# readhead.net
KiCad netlist of a schematic drawn in EAGLE
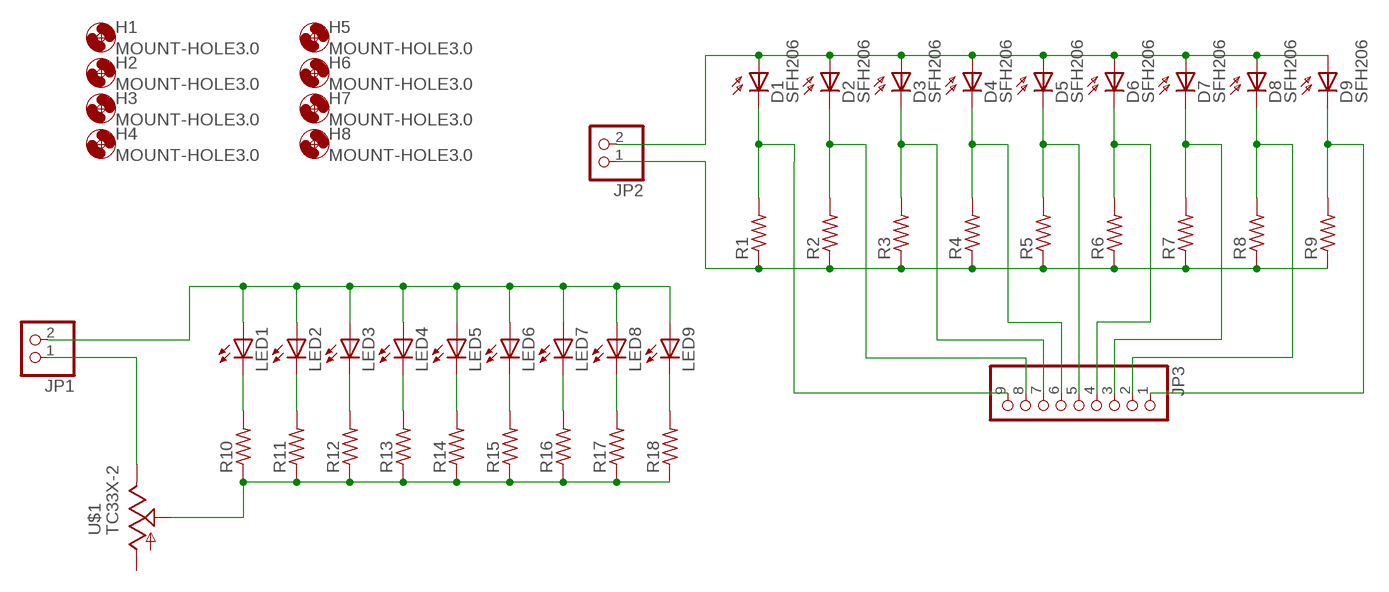
[diagram p0: schematic, sheet 1]

(export (version "E")
  (design (tool "Eeschema 10.0.6"))
  (components
    (comp (ref "D1")
      (value "SFH206")
      (footprint "eagle-import:SFH206")
      (fields (field (name "MPN") "SFH206K"))
      (libsource (lib "eagle-import") (part "SFH206"))
    )
    (comp (ref "D2")
      (value "SFH206")
      (footprint "eagle-import:SFH206")
      (fields (field (name "MPN") "SFH206K"))
      (libsource (lib "eagle-import") (part "SFH206"))
    )
    (comp (ref "D3")
      (value "SFH206")
      (footprint "eagle-import:SFH206")
      (fields (field (name "MPN") "SFH206K"))
      (libsource (lib "eagle-import") (part "SFH206"))
    )
    (comp (ref "D4")
      (value "SFH206")
      (footprint "eagle-import:SFH206")
      (fields (field (name "MPN") "SFH206K"))
      (libsource (lib "eagle-import") (part "SFH206"))
    )
    (comp (ref "D5")
      (value "SFH206")
      (footprint "eagle-import:SFH206")
      (fields (field (name "MPN") "SFH206K"))
      (libsource (lib "eagle-import") (part "SFH206"))
    )
    (comp (ref "D6")
      (value "SFH206")
      (footprint "eagle-import:SFH206")
      (fields (field (name "MPN") "SFH206K"))
      (libsource (lib "eagle-import") (part "SFH206"))
    )
    (comp (ref "D7")
      (value "SFH206")
      (footprint "eagle-import:SFH206")
      (fields (field (name "MPN") "SFH206K"))
      (libsource (lib "eagle-import") (part "SFH206"))
    )
    (comp (ref "D8")
      (value "SFH206")
      (footprint "eagle-import:SFH206")
      (fields (field (name "MPN") "SFH206K"))
      (libsource (lib "eagle-import") (part "SFH206"))
    )
    (comp (ref "D9")
      (value "SFH206")
      (footprint "eagle-import:SFH206")
      (fields (field (name "MPN") "SFH206K"))
      (libsource (lib "eagle-import") (part "SFH206"))
    )
    (comp (ref "H1")
      (value "MOUNT-HOLE3.0")
      (footprint "eagle-import:3,0")
      (libsource (lib "eagle-import") (part "MOUNT-HOLE3.0"))
    )
    (comp (ref "H2")
      (value "MOUNT-HOLE3.0")
      (footprint "eagle-import:3,0")
      (libsource (lib "eagle-import") (part "MOUNT-HOLE3.0"))
    )
    (comp (ref "H3")
      (value "MOUNT-HOLE3.0")
      (footprint "eagle-import:3,0")
      (libsource (lib "eagle-import") (part "MOUNT-HOLE3.0"))
    )
    (comp (ref "H4")
      (value "MOUNT-HOLE3.0")
      (footprint "eagle-import:3,0")
      (libsource (lib "eagle-import") (part "MOUNT-HOLE3.0"))
    )
    (comp (ref "H5")
      (value "MOUNT-HOLE3.0")
      (footprint "eagle-import:3,0")
      (libsource (lib "eagle-import") (part "MOUNT-HOLE3.0"))
    )
    (comp (ref "H6")
      (value "MOUNT-HOLE3.0")
      (footprint "eagle-import:3,0")
      (libsource (lib "eagle-import") (part "MOUNT-HOLE3.0"))
    )
    (comp (ref "H7")
      (value "MOUNT-HOLE3.0")
      (footprint "eagle-import:3,0")
      (libsource (lib "eagle-import") (part "MOUNT-HOLE3.0"))
    )
    (comp (ref "H8")
      (value "MOUNT-HOLE3.0")
      (footprint "eagle-import:3,0")
      (libsource (lib "eagle-import") (part "MOUNT-HOLE3.0"))
    )
    (comp (ref "JP1")
      (value "PINHD-1X2")
      (footprint "eagle-import:1X02")
      (libsource (lib "eagle-import") (part "PINHD-1X2"))
    )
    (comp (ref "JP2")
      (value "PINHD-1X2")
      (footprint "eagle-import:1X02")
      (libsource (lib "eagle-import") (part "PINHD-1X2"))
    )
    (comp (ref "JP3")
      (value "PINHD-1X9")
      (footprint "eagle-import:1X09")
      (libsource (lib "eagle-import") (part "PINHD-1X9"))
    )
    (comp (ref "LED1")
      (value "LED5MM")
      (footprint "eagle-import:LED5MM")
      (libsource (lib "eagle-import") (part "LED5MM"))
    )
    (comp (ref "LED2")
      (value "LED5MM")
      (footprint "eagle-import:LED5MM")
      (libsource (lib "eagle-import") (part "LED5MM"))
    )
    (comp (ref "LED3")
      (value "LED5MM")
      (footprint "eagle-import:LED5MM")
      (libsource (lib "eagle-import") (part "LED5MM"))
    )
    (comp (ref "LED4")
      (value "LED5MM")
      (footprint "eagle-import:LED5MM")
      (libsource (lib "eagle-import") (part "LED5MM"))
    )
    (comp (ref "LED5")
      (value "LED5MM")
      (footprint "eagle-import:LED5MM")
      (libsource (lib "eagle-import") (part "LED5MM"))
    )
    (comp (ref "LED6")
      (value "LED5MM")
      (footprint "eagle-import:LED5MM")
      (libsource (lib "eagle-import") (part "LED5MM"))
    )
    (comp (ref "LED7")
      (value "LED5MM")
      (footprint "eagle-import:LED5MM")
      (libsource (lib "eagle-import") (part "LED5MM"))
    )
    (comp (ref "LED8")
      (value "LED5MM")
      (footprint "eagle-import:LED5MM")
      (libsource (lib "eagle-import") (part "LED5MM"))
    )
    (comp (ref "LED9")
      (value "LED5MM")
      (footprint "eagle-import:LED5MM")
      (libsource (lib "eagle-import") (part "LED5MM"))
    )
    (comp (ref "R1")
      (value "R-US_R0805")
      (footprint "eagle-import:R0805")
      (libsource (lib "eagle-import") (part "R-US_R0805"))
    )
    (comp (ref "R2")
      (value "R-US_R0805")
      (footprint "eagle-import:R0805")
      (libsource (lib "eagle-import") (part "R-US_R0805"))
    )
    (comp (ref "R3")
      (value "R-US_R0805")
      (footprint "eagle-import:R0805")
      (libsource (lib "eagle-import") (part "R-US_R0805"))
    )
    (comp (ref "R4")
      (value "R-US_R0805")
      (footprint "eagle-import:R0805")
      (libsource (lib "eagle-import") (part "R-US_R0805"))
    )
    (comp (ref "R5")
      (value "R-US_R0805")
      (footprint "eagle-import:R0805")
      (libsource (lib "eagle-import") (part "R-US_R0805"))
    )
    (comp (ref "R6")
      (value "R-US_R0805")
      (footprint "eagle-import:R0805")
      (libsource (lib "eagle-import") (part "R-US_R0805"))
    )
    (comp (ref "R7")
      (value "R-US_R0805")
      (footprint "eagle-import:R0805")
      (libsource (lib "eagle-import") (part "R-US_R0805"))
    )
    (comp (ref "R8")
      (value "R-US_R0805")
      (footprint "eagle-import:R0805")
      (libsource (lib "eagle-import") (part "R-US_R0805"))
    )
    (comp (ref "R9")
      (value "R-US_R0805")
      (footprint "eagle-import:R0805")
      (libsource (lib "eagle-import") (part "R-US_R0805"))
    )
    (comp (ref "R10")
      (value "R-US_R0805")
      (footprint "eagle-import:R0805")
      (libsource (lib "eagle-import") (part "R-US_R0805"))
    )
    (comp (ref "R11")
      (value "R-US_R0805")
      (footprint "eagle-import:R0805")
      (libsource (lib "eagle-import") (part "R-US_R0805"))
    )
    (comp (ref "R12")
      (value "R-US_R0805")
      (footprint "eagle-import:R0805")
      (libsource (lib "eagle-import") (part "R-US_R0805"))
    )
    (comp (ref "R13")
      (value "R-US_R0805")
      (footprint "eagle-import:R0805")
      (libsource (lib "eagle-import") (part "R-US_R0805"))
    )
    (comp (ref "R14")
      (value "R-US_R0805")
      (footprint "eagle-import:R0805")
      (libsource (lib "eagle-import") (part "R-US_R0805"))
    )
    (comp (ref "R15")
      (value "R-US_R0805")
      (footprint "eagle-import:R0805")
      (libsource (lib "eagle-import") (part "R-US_R0805"))
    )
    (comp (ref "R16")
      (value "R-US_R0805")
      (footprint "eagle-import:R0805")
      (libsource (lib "eagle-import") (part "R-US_R0805"))
    )
    (comp (ref "R17")
      (value "R-US_R0805")
      (footprint "eagle-import:R0805")
      (libsource (lib "eagle-import") (part "R-US_R0805"))
    )
    (comp (ref "R18")
      (value "R-US_R0805")
      (footprint "eagle-import:R0805")
      (libsource (lib "eagle-import") (part "R-US_R0805"))
    )
    (comp (ref "U$1")
      (value "TC33X-2")
      (footprint "eagle-import:TC33X-2")
      (libsource (lib "eagle-import") (part "TC33X-2"))
    )
  )
  (nets
    (net (code "1") (name "Net-(D1-C)") (class "Default")
      (node (ref "D1") (pin "K") (pinfunction "C_K") (pintype "passive"))
      (node (ref "JP3") (pin "9") (pinfunction "9_9") (pintype "passive"))
      (node (ref "R1") (pin "2") (pinfunction "2_2") (pintype "passive"))
    )
    (net (code "2") (name "Net-(D1-PadA)") (class "Default")
      (node (ref "D1") (pin "A") (pinfunction "A_A") (pintype "passive"))
      (node (ref "D2") (pin "A") (pinfunction "A_A") (pintype "passive"))
      (node (ref "D3") (pin "A") (pinfunction "A_A") (pintype "passive"))
      (node (ref "D4") (pin "A") (pinfunction "A_A") (pintype "passive"))
      (node (ref "D5") (pin "A") (pinfunction "A_A") (pintype "passive"))
      (node (ref "D6") (pin "A") (pinfunction "A_A") (pintype "passive"))
      (node (ref "D7") (pin "A") (pinfunction "A_A") (pintype "passive"))
      (node (ref "D8") (pin "A") (pinfunction "A_A") (pintype "passive"))
      (node (ref "D9") (pin "A") (pinfunction "A_A") (pintype "passive"))
      (node (ref "JP2") (pin "2") (pinfunction "2_2") (pintype "passive"))
    )
    (net (code "3") (name "Net-(D2-C)") (class "Default")
      (node (ref "D2") (pin "K") (pinfunction "C_K") (pintype "passive"))
      (node (ref "JP3") (pin "8") (pinfunction "8_8") (pintype "passive"))
      (node (ref "R2") (pin "2") (pinfunction "2_2") (pintype "passive"))
    )
    (net (code "4") (name "Net-(D3-C)") (class "Default")
      (node (ref "D3") (pin "K") (pinfunction "C_K") (pintype "passive"))
      (node (ref "JP3") (pin "7") (pinfunction "7_7") (pintype "passive"))
      (node (ref "R3") (pin "2") (pinfunction "2_2") (pintype "passive"))
    )
    (net (code "5") (name "Net-(D4-C)") (class "Default")
      (node (ref "D4") (pin "K") (pinfunction "C_K") (pintype "passive"))
      (node (ref "JP3") (pin "6") (pinfunction "6_6") (pintype "passive"))
      (node (ref "R4") (pin "2") (pinfunction "2_2") (pintype "passive"))
    )
    (net (code "6") (name "Net-(D5-C)") (class "Default")
      (node (ref "D5") (pin "K") (pinfunction "C_K") (pintype "passive"))
      (node (ref "JP3") (pin "5") (pinfunction "5_5") (pintype "passive"))
      (node (ref "R5") (pin "2") (pinfunction "2_2") (pintype "passive"))
    )
    (net (code "7") (name "Net-(D6-C)") (class "Default")
      (node (ref "D6") (pin "K") (pinfunction "C_K") (pintype "passive"))
      (node (ref "JP3") (pin "4") (pinfunction "4_4") (pintype "passive"))
      (node (ref "R6") (pin "2") (pinfunction "2_2") (pintype "passive"))
    )
    (net (code "8") (name "Net-(D7-C)") (class "Default")
      (node (ref "D7") (pin "K") (pinfunction "C_K") (pintype "passive"))
      (node (ref "JP3") (pin "3") (pinfunction "3_3") (pintype "passive"))
      (node (ref "R7") (pin "2") (pinfunction "2_2") (pintype "passive"))
    )
    (net (code "9") (name "Net-(D8-C)") (class "Default")
      (node (ref "D8") (pin "K") (pinfunction "C_K") (pintype "passive"))
      (node (ref "JP3") (pin "2") (pinfunction "2_2") (pintype "passive"))
      (node (ref "R8") (pin "2") (pinfunction "2_2") (pintype "passive"))
    )
    (net (code "10") (name "Net-(D9-C)") (class "Default")
      (node (ref "D9") (pin "K") (pinfunction "C_K") (pintype "passive"))
      (node (ref "JP3") (pin "1") (pinfunction "1_1") (pintype "passive"))
      (node (ref "R9") (pin "2") (pinfunction "2_2") (pintype "passive"))
    )
    (net (code "11") (name "Net-(JP1-Pad2)") (class "Default")
      (node (ref "JP1") (pin "2") (pinfunction "2_2") (pintype "passive"))
      (node (ref "LED1") (pin "A") (pinfunction "A_A") (pintype "passive"))
      (node (ref "LED2") (pin "A") (pinfunction "A_A") (pintype "passive"))
      (node (ref "LED3") (pin "A") (pinfunction "A_A") (pintype "passive"))
      (node (ref "LED4") (pin "A") (pinfunction "A_A") (pintype "passive"))
      (node (ref "LED5") (pin "A") (pinfunction "A_A") (pintype "passive"))
      (node (ref "LED6") (pin "A") (pinfunction "A_A") (pintype "passive"))
      (node (ref "LED7") (pin "A") (pinfunction "A_A") (pintype "passive"))
      (node (ref "LED8") (pin "A") (pinfunction "A_A") (pintype "passive"))
      (node (ref "LED9") (pin "A") (pinfunction "A_A") (pintype "passive"))
    )
    (net (code "12") (name "Net-(JP2-Pad1)") (class "Default")
      (node (ref "JP2") (pin "1") (pinfunction "1_1") (pintype "passive"))
      (node (ref "R1") (pin "1") (pinfunction "1_1") (pintype "passive"))
      (node (ref "R2") (pin "1") (pinfunction "1_1") (pintype "passive"))
      (node (ref "R3") (pin "1") (pinfunction "1_1") (pintype "passive"))
      (node (ref "R4") (pin "1") (pinfunction "1_1") (pintype "passive"))
      (node (ref "R5") (pin "1") (pinfunction "1_1") (pintype "passive"))
      (node (ref "R6") (pin "1") (pinfunction "1_1") (pintype "passive"))
      (node (ref "R7") (pin "1") (pinfunction "1_1") (pintype "passive"))
      (node (ref "R8") (pin "1") (pinfunction "1_1") (pintype "passive"))
      (node (ref "R9") (pin "1") (pinfunction "1_1") (pintype "passive"))
    )
    (net (code "13") (name "Net-(LED1-C)") (class "Default")
      (node (ref "LED1") (pin "K") (pinfunction "C_K") (pintype "passive"))
      (node (ref "R10") (pin "2") (pinfunction "2_2") (pintype "passive"))
    )
    (net (code "14") (name "Net-(LED2-C)") (class "Default")
      (node (ref "LED2") (pin "K") (pinfunction "C_K") (pintype "passive"))
      (node (ref "R11") (pin "2") (pinfunction "2_2") (pintype "passive"))
    )
    (net (code "15") (name "Net-(LED3-C)") (class "Default")
      (node (ref "LED3") (pin "K") (pinfunction "C_K") (pintype "passive"))
      (node (ref "R12") (pin "2") (pinfunction "2_2") (pintype "passive"))
    )
    (net (code "16") (name "Net-(LED4-C)") (class "Default")
      (node (ref "LED4") (pin "K") (pinfunction "C_K") (pintype "passive"))
      (node (ref "R13") (pin "2") (pinfunction "2_2") (pintype "passive"))
    )
    (net (code "17") (name "Net-(LED5-C)") (class "Default")
      (node (ref "LED5") (pin "K") (pinfunction "C_K") (pintype "passive"))
      (node (ref "R14") (pin "2") (pinfunction "2_2") (pintype "passive"))
    )
    (net (code "18") (name "Net-(LED6-C)") (class "Default")
      (node (ref "LED6") (pin "K") (pinfunction "C_K") (pintype "passive"))
      (node (ref "R15") (pin "2") (pinfunction "2_2") (pintype "passive"))
    )
    (net (code "19") (name "Net-(LED7-C)") (class "Default")
      (node (ref "LED7") (pin "K") (pinfunction "C_K") (pintype "passive"))
      (node (ref "R16") (pin "2") (pinfunction "2_2") (pintype "passive"))
    )
    (net (code "20") (name "Net-(LED8-C)") (class "Default")
      (node (ref "LED8") (pin "K") (pinfunction "C_K") (pintype "passive"))
      (node (ref "R17") (pin "2") (pinfunction "2_2") (pintype "passive"))
    )
    (net (code "21") (name "Net-(LED9-C)") (class "Default")
      (node (ref "LED9") (pin "K") (pinfunction "C_K") (pintype "passive"))
      (node (ref "R18") (pin "2") (pinfunction "2_2") (pintype "passive"))
    )
    (net (code "22") (name "Net-(U$1-E)") (class "Default")
      (node (ref "JP1") (pin "1") (pinfunction "1_1") (pintype "passive"))
      (node (ref "U$1") (pin "P$3") (pinfunction "E_P$3") (pintype "passive"))
    )
    (net (code "23") (name "Net-(U$1-S)") (class "Default")
      (node (ref "R10") (pin "1") (pinfunction "1_1") (pintype "passive"))
      (node (ref "R11") (pin "1") (pinfunction "1_1") (pintype "passive"))
      (node (ref "R12") (pin "1") (pinfunction "1_1") (pintype "passive"))
      (node (ref "R13") (pin "1") (pinfunction "1_1") (pintype "passive"))
      (node (ref "R14") (pin "1") (pinfunction "1_1") (pintype "passive"))
      (node (ref "R15") (pin "1") (pinfunction "1_1") (pintype "passive"))
      (node (ref "R16") (pin "1") (pinfunction "1_1") (pintype "passive"))
      (node (ref "R17") (pin "1") (pinfunction "1_1") (pintype "passive"))
      (node (ref "R18") (pin "1") (pinfunction "1_1") (pintype "passive"))
      (node (ref "U$1") (pin "P$2") (pinfunction "S_P$2") (pintype "passive"))
    )
    (net (code "24") (name "unconnected-(U$1-A-PadP$1)") (class "Default")
      (node (ref "U$1") (pin "P$1") (pinfunction "A_P$1") (pintype "passive"))
    )
  )
)
